# basic-handheld-turbidimeter.net
KiCad netlist of a schematic drawn in EAGLE
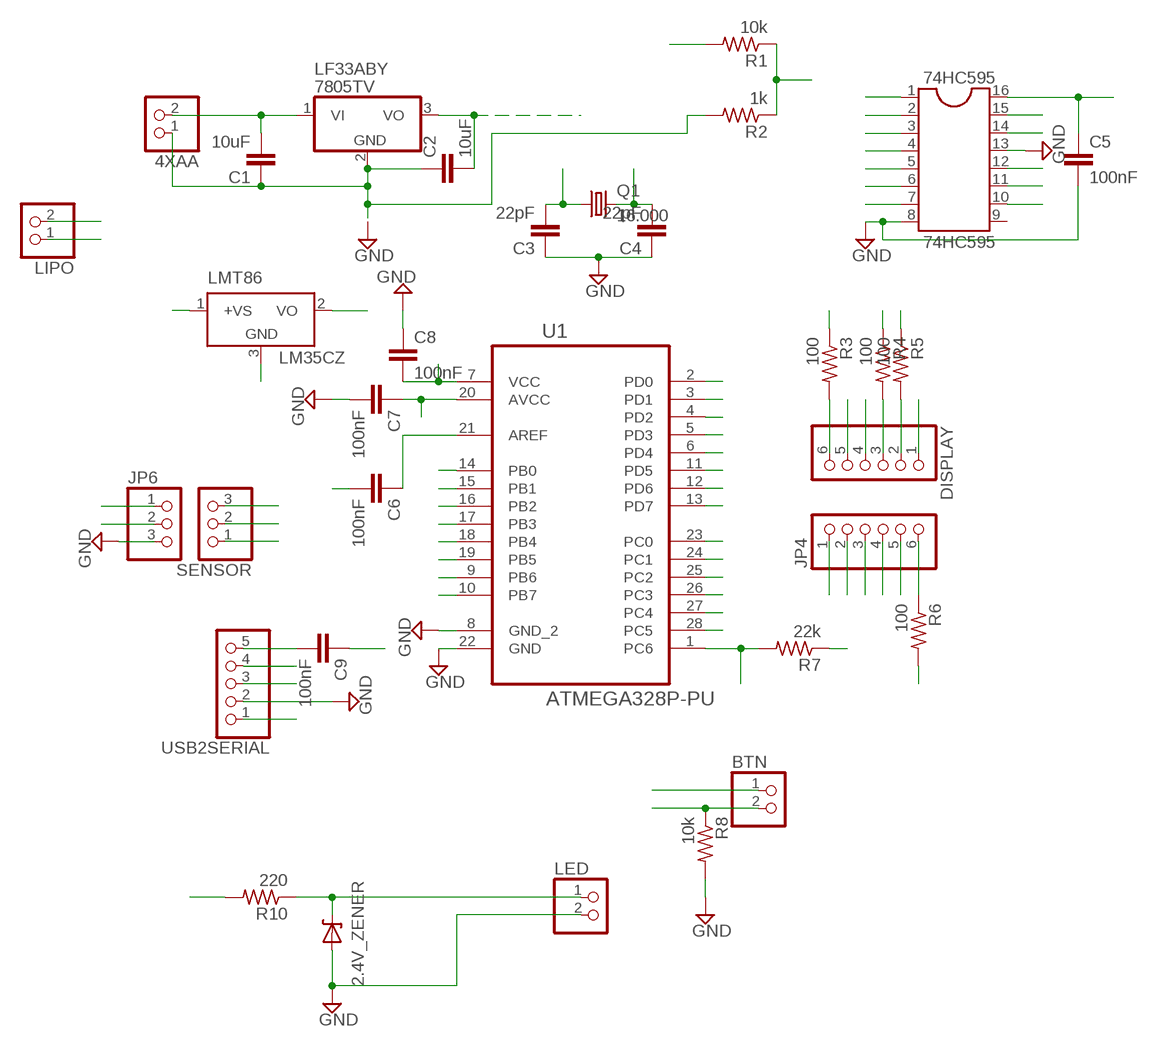
[diagram p0: schematic, sheet 1]

(export (version "E")
  (design (tool "Eeschema 10.0.6"))
  (components
    (comp (ref "2.4V_ZENER")
      (value "DNP")
      (footprint "eagle-import:DIODE-ZENER")
      (libsource (lib "eagle-import") (part "DIODE-ZENERPTH"))
    )
    (comp (ref "4XAA")
      (value "PINHD-1X2")
      (footprint "eagle-import:1X02")
      (libsource (lib "eagle-import") (part "PINHD-1X2"))
    )
    (comp (ref "74HC595")
      (value "74HC595")
      (footprint "eagle-import:DIL16")
      (libsource (lib "eagle-import") (part "DIL16"))
    )
    (comp (ref "BTN")
      (value "PINHD-1X2")
      (footprint "eagle-import:1X02")
      (libsource (lib "eagle-import") (part "PINHD-1X2"))
    )
    (comp (ref "C1")
      (value "10uF")
      (footprint "eagle-import:CAP-PTH-SMALLEZ")
      (libsource (lib "eagle-import") (part "CAPEZ"))
    )
    (comp (ref "C2")
      (value "10uF")
      (footprint "eagle-import:CAP-PTH-SMALLEZ")
      (libsource (lib "eagle-import") (part "CAPEZ"))
    )
    (comp (ref "C3")
      (value "22pF")
      (footprint "eagle-import:CAP-PTH-SMALLEZ")
      (libsource (lib "eagle-import") (part "CAPEZ"))
    )
    (comp (ref "C4")
      (value "22pF")
      (footprint "eagle-import:CAP-PTH-SMALLEZ")
      (libsource (lib "eagle-import") (part "CAPEZ"))
    )
    (comp (ref "C5")
      (value "100nF")
      (footprint "eagle-import:CAP-PTH-SMALLEZ")
      (libsource (lib "eagle-import") (part "CAPEZ"))
    )
    (comp (ref "C6")
      (value "100nF")
      (footprint "eagle-import:CAP-PTH-SMALLEZ")
      (libsource (lib "eagle-import") (part "CAPEZ"))
    )
    (comp (ref "C7")
      (value "100nF")
      (footprint "eagle-import:CAP-PTH-SMALLEZ")
      (libsource (lib "eagle-import") (part "CAPEZ"))
    )
    (comp (ref "C8")
      (value "100nF")
      (footprint "eagle-import:CAP-PTH-SMALLEZ")
      (libsource (lib "eagle-import") (part "CAPEZ"))
    )
    (comp (ref "C9")
      (value "100nF")
      (footprint "eagle-import:CAP-PTH-SMALLEZ")
      (libsource (lib "eagle-import") (part "CAPEZ"))
    )
    (comp (ref "DISPLAY")
      (value "PINHD-1X6")
      (footprint "eagle-import:1X06")
      (libsource (lib "eagle-import") (part "PINHD-1X6"))
    )
    (comp (ref "JP4")
      (value "PINHD-1X6")
      (footprint "eagle-import:1X06")
      (libsource (lib "eagle-import") (part "PINHD-1X6"))
    )
    (comp (ref "JP6")
      (value "PINHD-1X3")
      (footprint "eagle-import:1X03")
      (libsource (lib "eagle-import") (part "PINHD-1X3"))
    )
    (comp (ref "LED")
      (value "PINHD-1X2")
      (footprint "eagle-import:1X02")
      (libsource (lib "eagle-import") (part "PINHD-1X2"))
    )
    (comp (ref "LF33ABY")
      (value "7805TV")
      (footprint "eagle-import:TO220V")
      (libsource (lib "eagle-import") (part "78TV05"))
    )
    (comp (ref "LIPO")
      (value "PINHD-1X2")
      (footprint "eagle-import:1X02")
      (libsource (lib "eagle-import") (part "PINHD-1X2"))
    )
    (comp (ref "LMT86")
      (value "LM35CZ")
      (footprint "eagle-import:TO92")
      (libsource (lib "eagle-import") (part "LM35CZ"))
    )
    (comp (ref "Q1")
      (value "16.000")
      (footprint "eagle-import:HC49_S")
      (libsource (lib "eagle-import") (part "CRYSTALHC49S"))
    )
    (comp (ref "R1")
      (value "10k")
      (footprint "eagle-import:0207_12")
      (libsource (lib "eagle-import") (part "R-US_0207/12"))
    )
    (comp (ref "R2")
      (value "1k")
      (footprint "eagle-import:0207_12")
      (libsource (lib "eagle-import") (part "R-US_0207/12"))
    )
    (comp (ref "R3")
      (value "100")
      (footprint "eagle-import:0207_12")
      (libsource (lib "eagle-import") (part "R-US_0207/12"))
    )
    (comp (ref "R4")
      (value "100")
      (footprint "eagle-import:0207_12")
      (libsource (lib "eagle-import") (part "R-US_0207/12"))
    )
    (comp (ref "R5")
      (value "100")
      (footprint "eagle-import:0207_12")
      (libsource (lib "eagle-import") (part "R-US_0207/12"))
    )
    (comp (ref "R6")
      (value "100")
      (footprint "eagle-import:0207_12")
      (libsource (lib "eagle-import") (part "R-US_0207/12"))
    )
    (comp (ref "R7")
      (value "22k")
      (footprint "eagle-import:0207_12")
      (libsource (lib "eagle-import") (part "R-US_0207/12"))
    )
    (comp (ref "R8")
      (value "10k")
      (footprint "eagle-import:0207_12")
      (libsource (lib "eagle-import") (part "R-US_0207/12"))
    )
    (comp (ref "R10")
      (value "220")
      (footprint "eagle-import:0207_12")
      (libsource (lib "eagle-import") (part "R-US_0207/12"))
    )
    (comp (ref "SENSOR")
      (value "PINHD-1X3")
      (footprint "eagle-import:1X03")
      (libsource (lib "eagle-import") (part "PINHD-1X3"))
    )
    (comp (ref "U1")
      (value "ATMEGA328P-PU")
      (footprint "eagle-import:DIP254P762X457-28")
      (libsource (lib "eagle-import") (part "ATMEGA328P-PU"))
    )
    (comp (ref "USB2SERIAL")
      (value "PINHD-1X5")
      (footprint "eagle-import:1X05")
      (libsource (lib "eagle-import") (part "PINHD-1X5"))
    )
  )
  (nets
    (net (code "1") (name "/3V3") (class "Default")
      (node (ref "74HC595") (pin "10") (pinfunction "10_10") (pintype "passive"))
      (node (ref "74HC595") (pin "16") (pinfunction "16_16") (pintype "passive"))
      (node (ref "BTN") (pin "1") (pinfunction "1_1") (pintype "passive"))
      (node (ref "C2") (pin "2") (pinfunction "2_2") (pintype "passive"))
      (node (ref "C5") (pin "1") (pinfunction "1_1") (pintype "passive"))
      (node (ref "C7") (pin "1") (pinfunction "1_1") (pintype "passive"))
      (node (ref "C8") (pin "2") (pinfunction "2_2") (pintype "passive"))
      (node (ref "LF33ABY") (pin "3") (pinfunction "VO_3") (pintype "passive"))
      (node (ref "LIPO") (pin "2") (pinfunction "2_2") (pintype "passive"))
      (node (ref "LMT86") (pin "1") (pinfunction "+VS_1") (pintype "input"))
      (node (ref "R1") (pin "2") (pinfunction "2_2") (pintype "passive"))
      (node (ref "R7") (pin "1") (pinfunction "1_1") (pintype "passive"))
      (node (ref "SENSOR") (pin "1") (pinfunction "1_1") (pintype "passive"))
      (node (ref "U1") (pin "20") (pinfunction "AVCC_20") (pintype "power_in"))
      (node (ref "U1") (pin "7") (pinfunction "VCC_7") (pintype "power_in"))
      (node (ref "USB2SERIAL") (pin "1") (pinfunction "1_1") (pintype "passive"))
    )
    (net (code "2") (name "/595A") (class "Default")
      (node (ref "74HC595") (pin "15") (pinfunction "15_15") (pintype "passive"))
      (node (ref "DISPLAY") (pin "5") (pinfunction "5_5") (pintype "passive"))
    )
    (net (code "3") (name "/595B") (class "Default")
      (node (ref "74HC595") (pin "1") (pinfunction "1_1") (pintype "passive"))
      (node (ref "DISPLAY") (pin "1") (pinfunction "1_1") (pintype "passive"))
    )
    (net (code "4") (name "/595C") (class "Default")
      (node (ref "74HC595") (pin "2") (pinfunction "2_2") (pintype "passive"))
      (node (ref "JP4") (pin "4") (pinfunction "4_4") (pintype "passive"))
    )
    (net (code "5") (name "/595D") (class "Default")
      (node (ref "74HC595") (pin "3") (pinfunction "3_3") (pintype "passive"))
      (node (ref "JP4") (pin "2") (pinfunction "2_2") (pintype "passive"))
    )
    (net (code "6") (name "/595E") (class "Default")
      (node (ref "74HC595") (pin "4") (pinfunction "4_4") (pintype "passive"))
      (node (ref "JP4") (pin "1") (pinfunction "1_1") (pintype "passive"))
    )
    (net (code "7") (name "/595F") (class "Default")
      (node (ref "74HC595") (pin "5") (pinfunction "5_5") (pintype "passive"))
      (node (ref "DISPLAY") (pin "4") (pinfunction "4_4") (pintype "passive"))
    )
    (net (code "8") (name "/595G") (class "Default")
      (node (ref "74HC595") (pin "6") (pinfunction "6_6") (pintype "passive"))
      (node (ref "JP4") (pin "5") (pinfunction "5_5") (pintype "passive"))
    )
    (net (code "9") (name "/595H") (class "Default")
      (node (ref "74HC595") (pin "7") (pinfunction "7_7") (pintype "passive"))
      (node (ref "JP4") (pin "3") (pinfunction "3_3") (pintype "passive"))
    )
    (net (code "10") (name "/PB0") (class "Default")
      (node (ref "74HC595") (pin "11") (pinfunction "11_11") (pintype "passive"))
      (node (ref "U1") (pin "14") (pinfunction "PB0_14") (pintype "bidirectional"))
    )
    (net (code "11") (name "/PB1") (class "Default")
      (node (ref "SENSOR") (pin "3") (pinfunction "3_3") (pintype "passive"))
      (node (ref "U1") (pin "15") (pinfunction "PB1_15") (pintype "bidirectional"))
    )
    (net (code "12") (name "/PB2") (class "Default")
      (node (ref "R6") (pin "2") (pinfunction "2_2") (pintype "passive"))
      (node (ref "U1") (pin "16") (pinfunction "PB2_16") (pintype "bidirectional"))
    )
    (net (code "13") (name "/PB3") (class "Default")
      (node (ref "JP6") (pin "1") (pinfunction "1_1") (pintype "passive"))
      (node (ref "U1") (pin "17") (pinfunction "PB3_17") (pintype "bidirectional"))
    )
    (net (code "14") (name "/PB4") (class "Default")
      (node (ref "JP6") (pin "2") (pinfunction "2_2") (pintype "passive"))
      (node (ref "U1") (pin "18") (pinfunction "PB4_18") (pintype "bidirectional"))
    )
    (net (code "15") (name "/PB5") (class "Default")
      (node (ref "SENSOR") (pin "2") (pinfunction "2_2") (pintype "passive"))
      (node (ref "U1") (pin "19") (pinfunction "PB5_19") (pintype "bidirectional"))
    )
    (net (code "16") (name "/PB6") (class "Default")
      (node (ref "C3") (pin "2") (pinfunction "2_2") (pintype "passive"))
      (node (ref "Q1") (pin "1") (pinfunction "1_1") (pintype "passive"))
      (node (ref "U1") (pin "9") (pinfunction "PB6_9") (pintype "bidirectional"))
    )
    (net (code "17") (name "/PB7") (class "Default")
      (node (ref "C4") (pin "2") (pinfunction "2_2") (pintype "passive"))
      (node (ref "Q1") (pin "2") (pinfunction "2_2") (pintype "passive"))
      (node (ref "U1") (pin "10") (pinfunction "PB7_10") (pintype "bidirectional"))
    )
    (net (code "18") (name "/PC0") (class "Default")
      (node (ref "LMT86") (pin "2") (pinfunction "VO_2") (pintype "input"))
      (node (ref "U1") (pin "23") (pinfunction "PC0_23") (pintype "bidirectional"))
    )
    (net (code "19") (name "/PC1") (class "Default")
      (node (ref "R5") (pin "1") (pinfunction "1_1") (pintype "passive"))
      (node (ref "U1") (pin "24") (pinfunction "PC1_24") (pintype "bidirectional"))
    )
    (net (code "20") (name "/PC2") (class "Default")
      (node (ref "R4") (pin "1") (pinfunction "1_1") (pintype "passive"))
      (node (ref "U1") (pin "25") (pinfunction "PC2_25") (pintype "bidirectional"))
    )
    (net (code "21") (name "/PC3") (class "Default")
      (node (ref "R3") (pin "1") (pinfunction "1_1") (pintype "passive"))
      (node (ref "U1") (pin "26") (pinfunction "PC3_26") (pintype "bidirectional"))
    )
    (net (code "22") (name "/PC4") (class "Default")
      (node (ref "R1") (pin "1") (pinfunction "1_1") (pintype "passive"))
      (node (ref "R2") (pin "1") (pinfunction "1_1") (pintype "passive"))
      (node (ref "U1") (pin "27") (pinfunction "PC4_27") (pintype "bidirectional"))
    )
    (net (code "23") (name "/PC6") (class "Default")
      (node (ref "C9") (pin "1") (pinfunction "1_1") (pintype "passive"))
      (node (ref "R7") (pin "2") (pinfunction "2_2") (pintype "passive"))
      (node (ref "U1") (pin "1") (pinfunction "PC6_1") (pintype "bidirectional"))
    )
    (net (code "24") (name "/PD0") (class "Default")
      (node (ref "U1") (pin "2") (pinfunction "PD0_2") (pintype "bidirectional"))
      (node (ref "USB2SERIAL") (pin "3") (pinfunction "3_3") (pintype "passive"))
    )
    (net (code "25") (name "/PD1") (class "Default")
      (node (ref "U1") (pin "3") (pinfunction "PD1_3") (pintype "bidirectional"))
      (node (ref "USB2SERIAL") (pin "4") (pinfunction "4_4") (pintype "passive"))
    )
    (net (code "26") (name "/PD2") (class "Default")
      (node (ref "BTN") (pin "2") (pinfunction "2_2") (pintype "passive"))
      (node (ref "R8") (pin "1") (pinfunction "1_1") (pintype "passive"))
      (node (ref "U1") (pin "4") (pinfunction "PD2_4") (pintype "bidirectional"))
    )
    (net (code "27") (name "/PD4") (class "Default")
      (node (ref "R10") (pin "2") (pinfunction "2_2") (pintype "passive"))
      (node (ref "U1") (pin "6") (pinfunction "PD4_6") (pintype "bidirectional"))
    )
    (net (code "28") (name "/PD5") (class "Default")
      (node (ref "74HC595") (pin "14") (pinfunction "14_14") (pintype "passive"))
      (node (ref "U1") (pin "11") (pinfunction "PD5_11") (pintype "bidirectional"))
    )
    (net (code "29") (name "/PD6") (class "Default")
      (node (ref "74HC595") (pin "12") (pinfunction "12_12") (pintype "passive"))
      (node (ref "U1") (pin "12") (pinfunction "PD6_12") (pintype "bidirectional"))
    )
    (net (code "30") (name "GND") (class "Default")
      (node (ref "2.4V_ZENER") (pin "P$2") (pinfunction "A_P$2") (pintype "passive"))
      (node (ref "4XAA") (pin "1") (pinfunction "1_1") (pintype "passive"))
      (node (ref "74HC595") (pin "13") (pinfunction "13_13") (pintype "passive"))
      (node (ref "74HC595") (pin "8") (pinfunction "8_8") (pintype "passive"))
      (node (ref "C1") (pin "1") (pinfunction "1_1") (pintype "passive"))
      (node (ref "C2") (pin "1") (pinfunction "1_1") (pintype "passive"))
      (node (ref "C3") (pin "1") (pinfunction "1_1") (pintype "passive"))
      (node (ref "C4") (pin "1") (pinfunction "1_1") (pintype "passive"))
      (node (ref "C5") (pin "2") (pinfunction "2_2") (pintype "passive"))
      (node (ref "C6") (pin "2") (pinfunction "2_2") (pintype "passive"))
      (node (ref "C7") (pin "2") (pinfunction "2_2") (pintype "passive"))
      (node (ref "C8") (pin "1") (pinfunction "1_1") (pintype "passive"))
      (node (ref "JP6") (pin "3") (pinfunction "3_3") (pintype "passive"))
      (node (ref "LED") (pin "2") (pinfunction "2_2") (pintype "passive"))
      (node (ref "LF33ABY") (pin "2") (pinfunction "GND_2") (pintype "passive"))
      (node (ref "LIPO") (pin "1") (pinfunction "1_1") (pintype "passive"))
      (node (ref "LMT86") (pin "3") (pinfunction "GND_3") (pintype "power_in"))
      (node (ref "R2") (pin "2") (pinfunction "2_2") (pintype "passive"))
      (node (ref "R8") (pin "2") (pinfunction "2_2") (pintype "passive"))
      (node (ref "U1") (pin "13") (pinfunction "PD7_13") (pintype "bidirectional"))
      (node (ref "U1") (pin "22") (pinfunction "GND_22") (pintype "passive"))
      (node (ref "U1") (pin "5") (pinfunction "PD3_5") (pintype "bidirectional"))
      (node (ref "U1") (pin "8") (pinfunction "GND_2_8") (pintype "passive"))
      (node (ref "USB2SERIAL") (pin "2") (pinfunction "2_2") (pintype "passive"))
    )
    (net (code "31") (name "Net-(2.4V_ZENER-C)") (class "Default")
      (node (ref "2.4V_ZENER") (pin "P$1") (pinfunction "C_P$1") (pintype "passive"))
      (node (ref "LED") (pin "1") (pinfunction "1_1") (pintype "passive"))
      (node (ref "R10") (pin "1") (pinfunction "1_1") (pintype "passive"))
    )
    (net (code "32") (name "Net-(C9-Pad2)") (class "Default")
      (node (ref "C9") (pin "2") (pinfunction "2_2") (pintype "passive"))
      (node (ref "USB2SERIAL") (pin "5") (pinfunction "5_5") (pintype "passive"))
    )
    (net (code "33") (name "Net-(DISPLAY-Pad2)") (class "Default")
      (node (ref "DISPLAY") (pin "2") (pinfunction "2_2") (pintype "passive"))
      (node (ref "R5") (pin "2") (pinfunction "2_2") (pintype "passive"))
    )
    (net (code "34") (name "Net-(DISPLAY-Pad3)") (class "Default")
      (node (ref "DISPLAY") (pin "3") (pinfunction "3_3") (pintype "passive"))
      (node (ref "R4") (pin "2") (pinfunction "2_2") (pintype "passive"))
    )
    (net (code "35") (name "Net-(DISPLAY-Pad6)") (class "Default")
      (node (ref "DISPLAY") (pin "6") (pinfunction "6_6") (pintype "passive"))
      (node (ref "R3") (pin "2") (pinfunction "2_2") (pintype "passive"))
    )
    (net (code "36") (name "Net-(JP4-Pad6)") (class "Default")
      (node (ref "JP4") (pin "6") (pinfunction "6_6") (pintype "passive"))
      (node (ref "R6") (pin "1") (pinfunction "1_1") (pintype "passive"))
    )
    (net (code "37") (name "Net-(LF33ABY-VI)") (class "Default")
      (node (ref "4XAA") (pin "2") (pinfunction "2_2") (pintype "passive"))
      (node (ref "C1") (pin "2") (pinfunction "2_2") (pintype "passive"))
      (node (ref "LF33ABY") (pin "1") (pinfunction "VI_1") (pintype "input"))
    )
    (net (code "38") (name "Net-(U1-AREF)") (class "Default")
      (node (ref "C6") (pin "1") (pinfunction "1_1") (pintype "passive"))
      (node (ref "U1") (pin "21") (pinfunction "AREF_21") (pintype "input"))
    )
    (net (code "39") (name "unconnected-(74HC595-Pad9)") (class "Default")
      (node (ref "74HC595") (pin "9") (pinfunction "9_9") (pintype "passive"))
    )
    (net (code "40") (name "unconnected-(U1-PC5-Pad28)") (class "Default")
      (node (ref "U1") (pin "28") (pinfunction "PC5_28") (pintype "bidirectional"))
    )
  )
)
